# Codec_board.net
KiCad netlist of a schematic drawn in Altium Designer
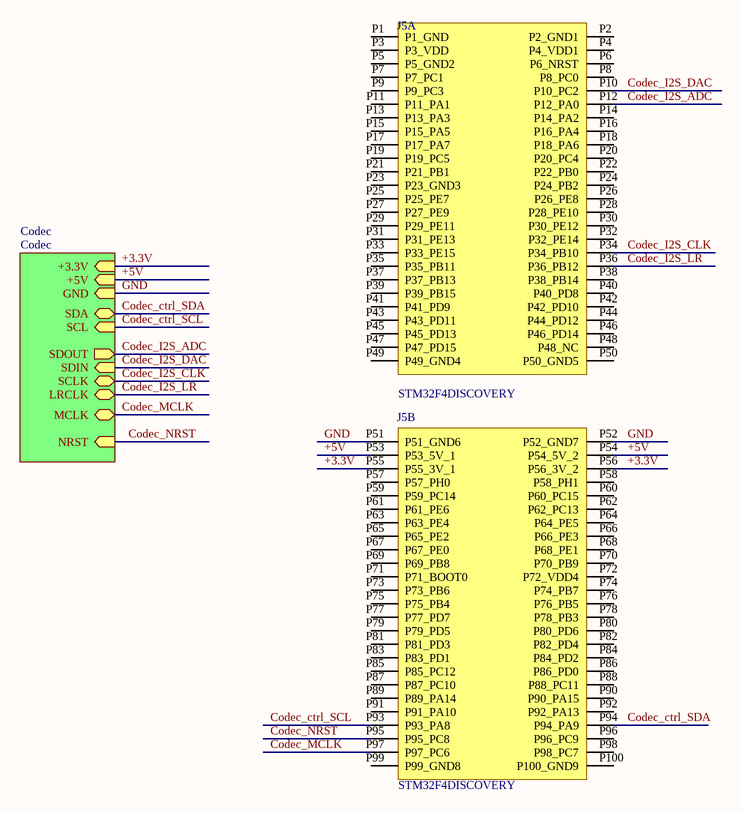
[diagram p0: Codec_board.SchDoc]

(export (version "E")
  (design (tool "Eeschema 10.0.6"))
  (components
    (comp (ref "J5")
      (value "STM32F4DISCOVERY")
      (footprint "STMICROELECTRONICS_STM32F4DISCOVERY_STM32F4DISCOVERY")
      (description "Development kit: ARM ST; pin strips, pin header; No.of")
      (fields (field (name "MF") "STMicroelectronics"))
      (libsource (lib "Codec_board") (part "STM32F4DISCOVERY"))
    )
  )
  (nets
    (net (code "1") (name "/+3.3V") (class "Default")
      (node (ref "J5") (pin "P55") (pinfunction "P55_3V_1_P55") (pintype "passive"))
      (node (ref "J5") (pin "P56") (pinfunction "P56_3V_2_P56") (pintype "passive"))
    )
    (net (code "2") (name "/+5V") (class "Default")
      (node (ref "J5") (pin "P53") (pinfunction "P53_5V_1_P53") (pintype "passive"))
      (node (ref "J5") (pin "P54") (pinfunction "P54_5V_2_P54") (pintype "passive"))
    )
    (net (code "3") (name "/Codec_I2S_ADC") (class "Default")
      (node (ref "J5") (pin "P12") (pinfunction "P12_PA0_P12") (pintype "passive"))
    )
    (net (code "4") (name "/Codec_I2S_CLK") (class "Default")
      (node (ref "J5") (pin "P34") (pinfunction "P34_PB10_P34") (pintype "passive"))
    )
    (net (code "5") (name "/Codec_I2S_DAC") (class "Default")
      (node (ref "J5") (pin "P10") (pinfunction "P10_PC2_P10") (pintype "passive"))
    )
    (net (code "6") (name "/Codec_I2S_LR") (class "Default")
      (node (ref "J5") (pin "P36") (pinfunction "P36_PB12_P36") (pintype "passive"))
    )
    (net (code "7") (name "/Codec_MCLK") (class "Default")
      (node (ref "J5") (pin "P97") (pinfunction "P97_PC6_P97") (pintype "passive"))
    )
    (net (code "8") (name "/Codec_NRST") (class "Default")
      (node (ref "J5") (pin "P95") (pinfunction "P95_PC8_P95") (pintype "passive"))
    )
    (net (code "9") (name "/Codec_ctrl_SCL") (class "Default")
      (node (ref "J5") (pin "P93") (pinfunction "P93_PA8_P93") (pintype "passive"))
    )
    (net (code "10") (name "/Codec_ctrl_SDA") (class "Default")
      (node (ref "J5") (pin "P94") (pinfunction "P94_PA9_P94") (pintype "passive"))
    )
    (net (code "11") (name "/GND") (class "Default")
      (node (ref "J5") (pin "P51") (pinfunction "P51_GND6_P51") (pintype "passive"))
      (node (ref "J5") (pin "P52") (pinfunction "P52_GND7_P52") (pintype "passive"))
    )
    (net (code "12") (name "unconnected-(J5A-P1_GND-PadP1)") (class "Default")
      (node (ref "J5") (pin "P1") (pinfunction "P1_GND_P1") (pintype "passive"))
    )
    (net (code "13") (name "unconnected-(J5A-P2_GND1-PadP2)") (class "Default")
      (node (ref "J5") (pin "P2") (pinfunction "P2_GND1_P2") (pintype "passive"))
    )
    (net (code "14") (name "unconnected-(J5A-P3_VDD-PadP3)") (class "Default")
      (node (ref "J5") (pin "P3") (pinfunction "P3_VDD_P3") (pintype "passive"))
    )
    (net (code "15") (name "unconnected-(J5A-P4_VDD1-PadP4)") (class "Default")
      (node (ref "J5") (pin "P4") (pinfunction "P4_VDD1_P4") (pintype "passive"))
    )
    (net (code "16") (name "unconnected-(J5A-P5_GND2-PadP5)") (class "Default")
      (node (ref "J5") (pin "P5") (pinfunction "P5_GND2_P5") (pintype "passive"))
    )
    (net (code "17") (name "unconnected-(J5A-P6_NRST-PadP6)") (class "Default")
      (node (ref "J5") (pin "P6") (pinfunction "P6_NRST_P6") (pintype "passive"))
    )
    (net (code "18") (name "unconnected-(J5A-P7_PC1-PadP7)") (class "Default")
      (node (ref "J5") (pin "P7") (pinfunction "P7_PC1_P7") (pintype "passive"))
    )
    (net (code "19") (name "unconnected-(J5A-P8_PC0-PadP8)") (class "Default")
      (node (ref "J5") (pin "P8") (pinfunction "P8_PC0_P8") (pintype "passive"))
    )
    (net (code "20") (name "unconnected-(J5A-P9_PC3-PadP9)") (class "Default")
      (node (ref "J5") (pin "P9") (pinfunction "P9_PC3_P9") (pintype "passive"))
    )
    (net (code "21") (name "unconnected-(J5A-P11_PA1-PadP11)") (class "Default")
      (node (ref "J5") (pin "P11") (pinfunction "P11_PA1_P11") (pintype "passive"))
    )
    (net (code "22") (name "unconnected-(J5A-P13_PA3-PadP13)") (class "Default")
      (node (ref "J5") (pin "P13") (pinfunction "P13_PA3_P13") (pintype "passive"))
    )
    (net (code "23") (name "unconnected-(J5A-P14_PA2-PadP14)") (class "Default")
      (node (ref "J5") (pin "P14") (pinfunction "P14_PA2_P14") (pintype "passive"))
    )
    (net (code "24") (name "unconnected-(J5A-P15_PA5-PadP15)") (class "Default")
      (node (ref "J5") (pin "P15") (pinfunction "P15_PA5_P15") (pintype "passive"))
    )
    (net (code "25") (name "unconnected-(J5A-P16_PA4-PadP16)") (class "Default")
      (node (ref "J5") (pin "P16") (pinfunction "P16_PA4_P16") (pintype "passive"))
    )
    (net (code "26") (name "unconnected-(J5A-P17_PA7-PadP17)") (class "Default")
      (node (ref "J5") (pin "P17") (pinfunction "P17_PA7_P17") (pintype "passive"))
    )
    (net (code "27") (name "unconnected-(J5A-P18_PA6-PadP18)") (class "Default")
      (node (ref "J5") (pin "P18") (pinfunction "P18_PA6_P18") (pintype "passive"))
    )
    (net (code "28") (name "unconnected-(J5A-P19_PC5-PadP19)") (class "Default")
      (node (ref "J5") (pin "P19") (pinfunction "P19_PC5_P19") (pintype "passive"))
    )
    (net (code "29") (name "unconnected-(J5A-P20_PC4-PadP20)") (class "Default")
      (node (ref "J5") (pin "P20") (pinfunction "P20_PC4_P20") (pintype "passive"))
    )
    (net (code "30") (name "unconnected-(J5A-P21_PB1-PadP21)") (class "Default")
      (node (ref "J5") (pin "P21") (pinfunction "P21_PB1_P21") (pintype "passive"))
    )
    (net (code "31") (name "unconnected-(J5A-P22_PB0-PadP22)") (class "Default")
      (node (ref "J5") (pin "P22") (pinfunction "P22_PB0_P22") (pintype "passive"))
    )
    (net (code "32") (name "unconnected-(J5A-P23_GND3-PadP23)") (class "Default")
      (node (ref "J5") (pin "P23") (pinfunction "P23_GND3_P23") (pintype "passive"))
    )
    (net (code "33") (name "unconnected-(J5A-P24_PB2-PadP24)") (class "Default")
      (node (ref "J5") (pin "P24") (pinfunction "P24_PB2_P24") (pintype "passive"))
    )
    (net (code "34") (name "unconnected-(J5A-P25_PE7-PadP25)") (class "Default")
      (node (ref "J5") (pin "P25") (pinfunction "P25_PE7_P25") (pintype "passive"))
    )
    (net (code "35") (name "unconnected-(J5A-P26_PE8-PadP26)") (class "Default")
      (node (ref "J5") (pin "P26") (pinfunction "P26_PE8_P26") (pintype "passive"))
    )
    (net (code "36") (name "unconnected-(J5A-P27_PE9-PadP27)") (class "Default")
      (node (ref "J5") (pin "P27") (pinfunction "P27_PE9_P27") (pintype "passive"))
    )
    (net (code "37") (name "unconnected-(J5A-P28_PE10-PadP28)") (class "Default")
      (node (ref "J5") (pin "P28") (pinfunction "P28_PE10_P28") (pintype "passive"))
    )
    (net (code "38") (name "unconnected-(J5A-P29_PE11-PadP29)") (class "Default")
      (node (ref "J5") (pin "P29") (pinfunction "P29_PE11_P29") (pintype "passive"))
    )
    (net (code "39") (name "unconnected-(J5A-P30_PE12-PadP30)") (class "Default")
      (node (ref "J5") (pin "P30") (pinfunction "P30_PE12_P30") (pintype "passive"))
    )
    (net (code "40") (name "unconnected-(J5A-P31_PE13-PadP31)") (class "Default")
      (node (ref "J5") (pin "P31") (pinfunction "P31_PE13_P31") (pintype "passive"))
    )
    (net (code "41") (name "unconnected-(J5A-P32_PE14-PadP32)") (class "Default")
      (node (ref "J5") (pin "P32") (pinfunction "P32_PE14_P32") (pintype "passive"))
    )
    (net (code "42") (name "unconnected-(J5A-P33_PE15-PadP33)") (class "Default")
      (node (ref "J5") (pin "P33") (pinfunction "P33_PE15_P33") (pintype "passive"))
    )
    (net (code "43") (name "unconnected-(J5A-P35_PB11-PadP35)") (class "Default")
      (node (ref "J5") (pin "P35") (pinfunction "P35_PB11_P35") (pintype "passive"))
    )
    (net (code "44") (name "unconnected-(J5A-P37_PB13-PadP37)") (class "Default")
      (node (ref "J5") (pin "P37") (pinfunction "P37_PB13_P37") (pintype "passive"))
    )
    (net (code "45") (name "unconnected-(J5A-P38_PB14-PadP38)") (class "Default")
      (node (ref "J5") (pin "P38") (pinfunction "P38_PB14_P38") (pintype "passive"))
    )
    (net (code "46") (name "unconnected-(J5A-P39_PB15-PadP39)") (class "Default")
      (node (ref "J5") (pin "P39") (pinfunction "P39_PB15_P39") (pintype "passive"))
    )
    (net (code "47") (name "unconnected-(J5A-P40_PD8-PadP40)") (class "Default")
      (node (ref "J5") (pin "P40") (pinfunction "P40_PD8_P40") (pintype "passive"))
    )
    (net (code "48") (name "unconnected-(J5A-P41_PD9-PadP41)") (class "Default")
      (node (ref "J5") (pin "P41") (pinfunction "P41_PD9_P41") (pintype "passive"))
    )
    (net (code "49") (name "unconnected-(J5A-P42_PD10-PadP42)") (class "Default")
      (node (ref "J5") (pin "P42") (pinfunction "P42_PD10_P42") (pintype "passive"))
    )
    (net (code "50") (name "unconnected-(J5A-P43_PD11-PadP43)") (class "Default")
      (node (ref "J5") (pin "P43") (pinfunction "P43_PD11_P43") (pintype "passive"))
    )
    (net (code "51") (name "unconnected-(J5A-P44_PD12-PadP44)") (class "Default")
      (node (ref "J5") (pin "P44") (pinfunction "P44_PD12_P44") (pintype "passive"))
    )
    (net (code "52") (name "unconnected-(J5A-P45_PD13-PadP45)") (class "Default")
      (node (ref "J5") (pin "P45") (pinfunction "P45_PD13_P45") (pintype "passive"))
    )
    (net (code "53") (name "unconnected-(J5A-P46_PD14-PadP46)") (class "Default")
      (node (ref "J5") (pin "P46") (pinfunction "P46_PD14_P46") (pintype "passive"))
    )
    (net (code "54") (name "unconnected-(J5A-P47_PD15-PadP47)") (class "Default")
      (node (ref "J5") (pin "P47") (pinfunction "P47_PD15_P47") (pintype "passive"))
    )
    (net (code "55") (name "unconnected-(J5A-P48_NC-PadP48)") (class "Default")
      (node (ref "J5") (pin "P48") (pinfunction "P48_NC_P48") (pintype "passive"))
    )
    (net (code "56") (name "unconnected-(J5A-P49_GND4-PadP49)") (class "Default")
      (node (ref "J5") (pin "P49") (pinfunction "P49_GND4_P49") (pintype "passive"))
    )
    (net (code "57") (name "unconnected-(J5A-P50_GND5-PadP50)") (class "Default")
      (node (ref "J5") (pin "P50") (pinfunction "P50_GND5_P50") (pintype "passive"))
    )
    (net (code "58") (name "unconnected-(J5B-P57_PH0-PadP57)") (class "Default")
      (node (ref "J5") (pin "P57") (pinfunction "P57_PH0_P57") (pintype "passive"))
    )
    (net (code "59") (name "unconnected-(J5B-P58_PH1-PadP58)") (class "Default")
      (node (ref "J5") (pin "P58") (pinfunction "P58_PH1_P58") (pintype "passive"))
    )
    (net (code "60") (name "unconnected-(J5B-P59_PC14-PadP59)") (class "Default")
      (node (ref "J5") (pin "P59") (pinfunction "P59_PC14_P59") (pintype "passive"))
    )
    (net (code "61") (name "unconnected-(J5B-P60_PC15-PadP60)") (class "Default")
      (node (ref "J5") (pin "P60") (pinfunction "P60_PC15_P60") (pintype "passive"))
    )
    (net (code "62") (name "unconnected-(J5B-P61_PE6-PadP61)") (class "Default")
      (node (ref "J5") (pin "P61") (pinfunction "P61_PE6_P61") (pintype "passive"))
    )
    (net (code "63") (name "unconnected-(J5B-P62_PC13-PadP62)") (class "Default")
      (node (ref "J5") (pin "P62") (pinfunction "P62_PC13_P62") (pintype "passive"))
    )
    (net (code "64") (name "unconnected-(J5B-P63_PE4-PadP63)") (class "Default")
      (node (ref "J5") (pin "P63") (pinfunction "P63_PE4_P63") (pintype "passive"))
    )
    (net (code "65") (name "unconnected-(J5B-P64_PE5-PadP64)") (class "Default")
      (node (ref "J5") (pin "P64") (pinfunction "P64_PE5_P64") (pintype "passive"))
    )
    (net (code "66") (name "unconnected-(J5B-P65_PE2-PadP65)") (class "Default")
      (node (ref "J5") (pin "P65") (pinfunction "P65_PE2_P65") (pintype "passive"))
    )
    (net (code "67") (name "unconnected-(J5B-P66_PE3-PadP66)") (class "Default")
      (node (ref "J5") (pin "P66") (pinfunction "P66_PE3_P66") (pintype "passive"))
    )
    (net (code "68") (name "unconnected-(J5B-P67_PE0-PadP67)") (class "Default")
      (node (ref "J5") (pin "P67") (pinfunction "P67_PE0_P67") (pintype "passive"))
    )
    (net (code "69") (name "unconnected-(J5B-P68_PE1-PadP68)") (class "Default")
      (node (ref "J5") (pin "P68") (pinfunction "P68_PE1_P68") (pintype "passive"))
    )
    (net (code "70") (name "unconnected-(J5B-P69_PB8-PadP69)") (class "Default")
      (node (ref "J5") (pin "P69") (pinfunction "P69_PB8_P69") (pintype "passive"))
    )
    (net (code "71") (name "unconnected-(J5B-P70_PB9-PadP70)") (class "Default")
      (node (ref "J5") (pin "P70") (pinfunction "P70_PB9_P70") (pintype "passive"))
    )
    (net (code "72") (name "unconnected-(J5B-P71_BOOT0-PadP71)") (class "Default")
      (node (ref "J5") (pin "P71") (pinfunction "P71_BOOT0_P71") (pintype "passive"))
    )
    (net (code "73") (name "unconnected-(J5B-P72_VDD4-PadP72)") (class "Default")
      (node (ref "J5") (pin "P72") (pinfunction "P72_VDD4_P72") (pintype "passive"))
    )
    (net (code "74") (name "unconnected-(J5B-P73_PB6-PadP73)") (class "Default")
      (node (ref "J5") (pin "P73") (pinfunction "P73_PB6_P73") (pintype "passive"))
    )
    (net (code "75") (name "unconnected-(J5B-P74_PB7-PadP74)") (class "Default")
      (node (ref "J5") (pin "P74") (pinfunction "P74_PB7_P74") (pintype "passive"))
    )
    (net (code "76") (name "unconnected-(J5B-P75_PB4-PadP75)") (class "Default")
      (node (ref "J5") (pin "P75") (pinfunction "P75_PB4_P75") (pintype "passive"))
    )
    (net (code "77") (name "unconnected-(J5B-P76_PB5-PadP76)") (class "Default")
      (node (ref "J5") (pin "P76") (pinfunction "P76_PB5_P76") (pintype "passive"))
    )
    (net (code "78") (name "unconnected-(J5B-P77_PD7-PadP77)") (class "Default")
      (node (ref "J5") (pin "P77") (pinfunction "P77_PD7_P77") (pintype "passive"))
    )
    (net (code "79") (name "unconnected-(J5B-P78_PB3-PadP78)") (class "Default")
      (node (ref "J5") (pin "P78") (pinfunction "P78_PB3_P78") (pintype "passive"))
    )
    (net (code "80") (name "unconnected-(J5B-P79_PD5-PadP79)") (class "Default")
      (node (ref "J5") (pin "P79") (pinfunction "P79_PD5_P79") (pintype "passive"))
    )
    (net (code "81") (name "unconnected-(J5B-P80_PD6-PadP80)") (class "Default")
      (node (ref "J5") (pin "P80") (pinfunction "P80_PD6_P80") (pintype "passive"))
    )
    (net (code "82") (name "unconnected-(J5B-P81_PD3-PadP81)") (class "Default")
      (node (ref "J5") (pin "P81") (pinfunction "P81_PD3_P81") (pintype "passive"))
    )
    (net (code "83") (name "unconnected-(J5B-P82_PD4-PadP82)") (class "Default")
      (node (ref "J5") (pin "P82") (pinfunction "P82_PD4_P82") (pintype "passive"))
    )
    (net (code "84") (name "unconnected-(J5B-P83_PD1-PadP83)") (class "Default")
      (node (ref "J5") (pin "P83") (pinfunction "P83_PD1_P83") (pintype "passive"))
    )
    (net (code "85") (name "unconnected-(J5B-P84_PD2-PadP84)") (class "Default")
      (node (ref "J5") (pin "P84") (pinfunction "P84_PD2_P84") (pintype "passive"))
    )
    (net (code "86") (name "unconnected-(J5B-P85_PC12-PadP85)") (class "Default")
      (node (ref "J5") (pin "P85") (pinfunction "P85_PC12_P85") (pintype "passive"))
    )
    (net (code "87") (name "unconnected-(J5B-P86_PD0-PadP86)") (class "Default")
      (node (ref "J5") (pin "P86") (pinfunction "P86_PD0_P86") (pintype "passive"))
    )
    (net (code "88") (name "unconnected-(J5B-P87_PC10-PadP87)") (class "Default")
      (node (ref "J5") (pin "P87") (pinfunction "P87_PC10_P87") (pintype "passive"))
    )
    (net (code "89") (name "unconnected-(J5B-P88_PC11-PadP88)") (class "Default")
      (node (ref "J5") (pin "P88") (pinfunction "P88_PC11_P88") (pintype "passive"))
    )
    (net (code "90") (name "unconnected-(J5B-P89_PA14-PadP89)") (class "Default")
      (node (ref "J5") (pin "P89") (pinfunction "P89_PA14_P89") (pintype "passive"))
    )
    (net (code "91") (name "unconnected-(J5B-P90_PA15-PadP90)") (class "Default")
      (node (ref "J5") (pin "P90") (pinfunction "P90_PA15_P90") (pintype "passive"))
    )
    (net (code "92") (name "unconnected-(J5B-P91_PA10-PadP91)") (class "Default")
      (node (ref "J5") (pin "P91") (pinfunction "P91_PA10_P91") (pintype "passive"))
    )
    (net (code "93") (name "unconnected-(J5B-P92_PA13-PadP92)") (class "Default")
      (node (ref "J5") (pin "P92") (pinfunction "P92_PA13_P92") (pintype "passive"))
    )
    (net (code "94") (name "unconnected-(J5B-P96_PC9-PadP96)") (class "Default")
      (node (ref "J5") (pin "P96") (pinfunction "P96_PC9_P96") (pintype "passive"))
    )
    (net (code "95") (name "unconnected-(J5B-P98_PC7-PadP98)") (class "Default")
      (node (ref "J5") (pin "P98") (pinfunction "P98_PC7_P98") (pintype "passive"))
    )
    (net (code "96") (name "unconnected-(J5B-P99_GND8-PadP99)") (class "Default")
      (node (ref "J5") (pin "P99") (pinfunction "P99_GND8_P99") (pintype "passive"))
    )
    (net (code "97") (name "unconnected-(J5B-P100_GND9-PadP100)") (class "Default")
      (node (ref "J5") (pin "P100") (pinfunction "P100_GND9_P100") (pintype "passive"))
    )
  )
)
